# Sheet1.net
KiCad netlist of a schematic drawn in Altium Designer
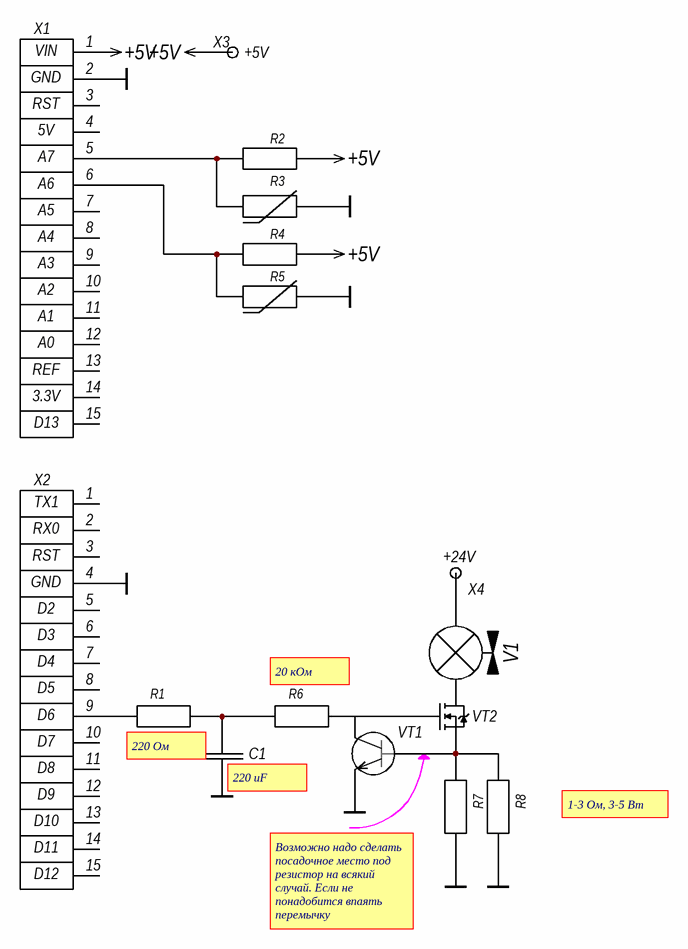
[diagram p0: Sheet1.SchDoc]

(export (version "E")
  (design (tool "Eeschema 10.0.6"))
  (components
    (comp (ref "C1")
      (value "Ceramic AVX")
      (footprint "Конденсаторы_(Imp):0805")
      (description "Конденсатор керамический")
      (libsource (lib "Конденсаторы_(Imp)") (part "Ceramic AVX"))
    )
    (comp (ref "R1")
      (value "Р1-8В-0,75-220 Ом")
      (footprint "Резисторы_(Ru):R-1206-0.25Вт")
      (description "Резистор")
      (libsource (lib "Резисторы_(Ru)") (part "R1-8B"))
    )
    (comp (ref "R2")
      (value "Р1-8В 20 кОм")
      (footprint "Резисторы_(Ru):R-1206-0.25Вт")
      (description "Резистор")
      (libsource (lib "Резисторы_(Ru)") (part "R1-8B"))
    )
    (comp (ref "R3")
      (value "B57861S0303F045")
      (footprint "Вилка на плату")
      (description "Резистор")
      (libsource (lib "Резисторы_(Ru)") (part "Термистор"))
    )
    (comp (ref "R4")
      (value "Р1-8В 20 кОм")
      (footprint "Резисторы_(Ru):R-1206-0.25Вт")
      (description "Резистор")
      (libsource (lib "Резисторы_(Ru)") (part "R1-8B"))
    )
    (comp (ref "R5")
      (value "B57861S0303F045")
      (footprint "Вилка на плату")
      (description "Резистор")
      (libsource (lib "Резисторы_(Ru)") (part "Термистор"))
    )
    (comp (ref "R6")
      (value "Р1-8В-0,75-20 кОм")
      (footprint "Резисторы_(Ru):R-1206-0.25Вт")
      (description "Резистор")
      (libsource (lib "Резисторы_(Ru)") (part "R1-8B"))
    )
    (comp (ref "R7")
      (value "Р1-8В-2-3 Ом")
      (footprint "Резисторы_(Ru):R-4020-2.0Вт")
      (description "Резистор")
      (libsource (lib "Резисторы_(Ru)") (part "R1-8B"))
    )
    (comp (ref "R8")
      (value "Р1-8В-2-3 Ом")
      (footprint "Резисторы_(Ru):R-4020-2.0Вт")
      (description "Резистор")
      (libsource (lib "Резисторы_(Ru)") (part "R1-8B"))
    )
    (comp (ref "V1")
      (value "Обозначение при заказе")
      (footprint "Вилка на плату")
      (description "Описание свойств компонента")
      (libsource (lib "Schlib1") (part "VALVE"))
    )
    (comp (ref "VT1")
      (value "C33740")
      (footprint "Transistor")
      (description "Транзистор N-P-N")
      (libsource (lib "Полупроводники_(Ru)") (part "2T665A91"))
    )
    (comp (ref "VT2")
      (value "IRF530N")
      (footprint "MOSFET")
      (description "MOSFET")
      (libsource (lib "Полупроводники_(Ru)") (part "MOSFET"))
    )
    (comp (ref "X1") (value "SOCKET") (footprint "SOCKET") (libsource (lib "Schlib1") (part "SOCKET")))
    (comp (ref "X2") (value "SOCKET") (footprint "SOCKET") (libsource (lib "Schlib1") (part "SOCKET")))
    (comp (ref "X3")
      (value "+5V")
      (footprint "Вилка на плату")
      (libsource (lib "Контактные отв. и пл.") (part "Контакт отверстие"))
    )
    (comp (ref "X4")
      (value "+24V")
      (footprint "Вилка на плату")
      (libsource (lib "Контактные отв. и пл.") (part "Контакт отверстие"))
    )
  )
  (nets
    (net (code "1") (name "+5V") (class "Default")
      (node (ref "R2") (pin "1") (pinfunction "1_1") (pintype "passive"))
      (node (ref "R4") (pin "1") (pinfunction "1_1") (pintype "passive"))
      (node (ref "X1") (pin "1") (pinfunction "1_1") (pintype "passive"))
      (node (ref "X3") (pin "1") (pintype "passive"))
    )
    (net (code "2") (name "GND") (class "Default")
      (node (ref "C1") (pin "2") (pinfunction "2_2") (pintype "passive"))
      (node (ref "R3") (pin "2") (pinfunction "2_2") (pintype "passive"))
      (node (ref "R5") (pin "2") (pinfunction "2_2") (pintype "passive"))
      (node (ref "R7") (pin "2") (pinfunction "2_2") (pintype "passive"))
      (node (ref "R8") (pin "2") (pinfunction "2_2") (pintype "passive"))
      (node (ref "VT1") (pin "1") (pinfunction "E_1") (pintype "passive"))
      (node (ref "X1") (pin "2") (pinfunction "2_2") (pintype "passive"))
      (node (ref "X2") (pin "4") (pinfunction "4_4") (pintype "passive"))
    )
    (net (code "3") (name "Net-(C1-Pad1)") (class "Default")
      (node (ref "C1") (pin "1") (pinfunction "1_1") (pintype "passive"))
      (node (ref "R1") (pin "2") (pinfunction "2_2") (pintype "passive"))
      (node (ref "R6") (pin "1") (pinfunction "1_1") (pintype "passive"))
    )
    (net (code "4") (name "Net-(R1-Pad1)") (class "Default")
      (node (ref "R1") (pin "1") (pinfunction "1_1") (pintype "passive"))
      (node (ref "X2") (pin "9") (pinfunction "9_9") (pintype "passive"))
    )
    (net (code "5") (name "Net-(R2-Pad2)") (class "Default")
      (node (ref "R2") (pin "2") (pinfunction "2_2") (pintype "passive"))
      (node (ref "R3") (pin "1") (pinfunction "1_1") (pintype "passive"))
      (node (ref "X1") (pin "5") (pinfunction "5_5") (pintype "passive"))
    )
    (net (code "6") (name "Net-(R4-Pad2)") (class "Default")
      (node (ref "R4") (pin "2") (pinfunction "2_2") (pintype "passive"))
      (node (ref "R5") (pin "1") (pinfunction "1_1") (pintype "passive"))
      (node (ref "X1") (pin "6") (pinfunction "6_6") (pintype "passive"))
    )
    (net (code "7") (name "Net-(V1-Pad1)") (class "Default")
      (node (ref "V1") (pin "1") (pinfunction "1_1") (pintype "passive"))
      (node (ref "X4") (pin "1") (pintype "passive"))
    )
    (net (code "8") (name "Net-(VT1-B)") (class "Default")
      (node (ref "R7") (pin "1") (pinfunction "1_1") (pintype "passive"))
      (node (ref "R8") (pin "1") (pinfunction "1_1") (pintype "passive"))
      (node (ref "VT1") (pin "2") (pinfunction "B_2") (pintype "passive"))
      (node (ref "VT2") (pin "3") (pinfunction "S_3") (pintype "passive"))
    )
    (net (code "9") (name "Net-(VT1-C)") (class "Default")
      (node (ref "R6") (pin "2") (pinfunction "2_2") (pintype "passive"))
      (node (ref "VT1") (pin "3") (pinfunction "C_3") (pintype "passive"))
      (node (ref "VT2") (pin "1") (pinfunction "G_1") (pintype "passive"))
    )
    (net (code "10") (name "Net-(VT2-D)") (class "Default")
      (node (ref "V1") (pin "2") (pinfunction "2_2") (pintype "passive"))
      (node (ref "VT2") (pin "2") (pinfunction "D_2") (pintype "passive"))
    )
    (net (code "11") (name "unconnected-(X1-Pad3)") (class "Default")
      (node (ref "X1") (pin "3") (pinfunction "3_3") (pintype "passive"))
    )
    (net (code "12") (name "unconnected-(X1-Pad4)") (class "Default")
      (node (ref "X1") (pin "4") (pinfunction "4_4") (pintype "passive"))
    )
    (net (code "13") (name "unconnected-(X1-Pad7)") (class "Default")
      (node (ref "X1") (pin "7") (pinfunction "7_7") (pintype "passive"))
    )
    (net (code "14") (name "unconnected-(X1-Pad8)") (class "Default")
      (node (ref "X1") (pin "8") (pinfunction "8_8") (pintype "passive"))
    )
    (net (code "15") (name "unconnected-(X1-Pad9)") (class "Default")
      (node (ref "X1") (pin "9") (pinfunction "9_9") (pintype "passive"))
    )
    (net (code "16") (name "unconnected-(X1-Pad10)") (class "Default")
      (node (ref "X1") (pin "10") (pinfunction "10_10") (pintype "passive"))
    )
    (net (code "17") (name "unconnected-(X1-Pad11)") (class "Default")
      (node (ref "X1") (pin "11") (pinfunction "11_11") (pintype "passive"))
    )
    (net (code "18") (name "unconnected-(X1-Pad12)") (class "Default")
      (node (ref "X1") (pin "12") (pinfunction "12_12") (pintype "passive"))
    )
    (net (code "19") (name "unconnected-(X1-Pad13)") (class "Default")
      (node (ref "X1") (pin "13") (pinfunction "13_13") (pintype "passive"))
    )
    (net (code "20") (name "unconnected-(X1-Pad14)") (class "Default")
      (node (ref "X1") (pin "14") (pinfunction "14_14") (pintype "passive"))
    )
    (net (code "21") (name "unconnected-(X1-Pad15)") (class "Default")
      (node (ref "X1") (pin "15") (pinfunction "15_15") (pintype "passive"))
    )
    (net (code "22") (name "unconnected-(X2-Pad1)") (class "Default")
      (node (ref "X2") (pin "1") (pinfunction "1_1") (pintype "passive"))
    )
    (net (code "23") (name "unconnected-(X2-Pad2)") (class "Default")
      (node (ref "X2") (pin "2") (pinfunction "2_2") (pintype "passive"))
    )
    (net (code "24") (name "unconnected-(X2-Pad3)") (class "Default")
      (node (ref "X2") (pin "3") (pinfunction "3_3") (pintype "passive"))
    )
    (net (code "25") (name "unconnected-(X2-Pad5)") (class "Default")
      (node (ref "X2") (pin "5") (pinfunction "5_5") (pintype "passive"))
    )
    (net (code "26") (name "unconnected-(X2-Pad6)") (class "Default")
      (node (ref "X2") (pin "6") (pinfunction "6_6") (pintype "passive"))
    )
    (net (code "27") (name "unconnected-(X2-Pad7)") (class "Default")
      (node (ref "X2") (pin "7") (pinfunction "7_7") (pintype "passive"))
    )
    (net (code "28") (name "unconnected-(X2-Pad8)") (class "Default")
      (node (ref "X2") (pin "8") (pinfunction "8_8") (pintype "passive"))
    )
    (net (code "29") (name "unconnected-(X2-Pad10)") (class "Default")
      (node (ref "X2") (pin "10") (pinfunction "10_10") (pintype "passive"))
    )
    (net (code "30") (name "unconnected-(X2-Pad11)") (class "Default")
      (node (ref "X2") (pin "11") (pinfunction "11_11") (pintype "passive"))
    )
    (net (code "31") (name "unconnected-(X2-Pad12)") (class "Default")
      (node (ref "X2") (pin "12") (pinfunction "12_12") (pintype "passive"))
    )
    (net (code "32") (name "unconnected-(X2-Pad13)") (class "Default")
      (node (ref "X2") (pin "13") (pinfunction "13_13") (pintype "passive"))
    )
    (net (code "33") (name "unconnected-(X2-Pad14)") (class "Default")
      (node (ref "X2") (pin "14") (pinfunction "14_14") (pintype "passive"))
    )
    (net (code "34") (name "unconnected-(X2-Pad15)") (class "Default")
      (node (ref "X2") (pin "15") (pinfunction "15_15") (pintype "passive"))
    )
  )
)
